# Page05_DDR4L_eMMC.net
KiCad netlist of a schematic drawn in Altium Designer
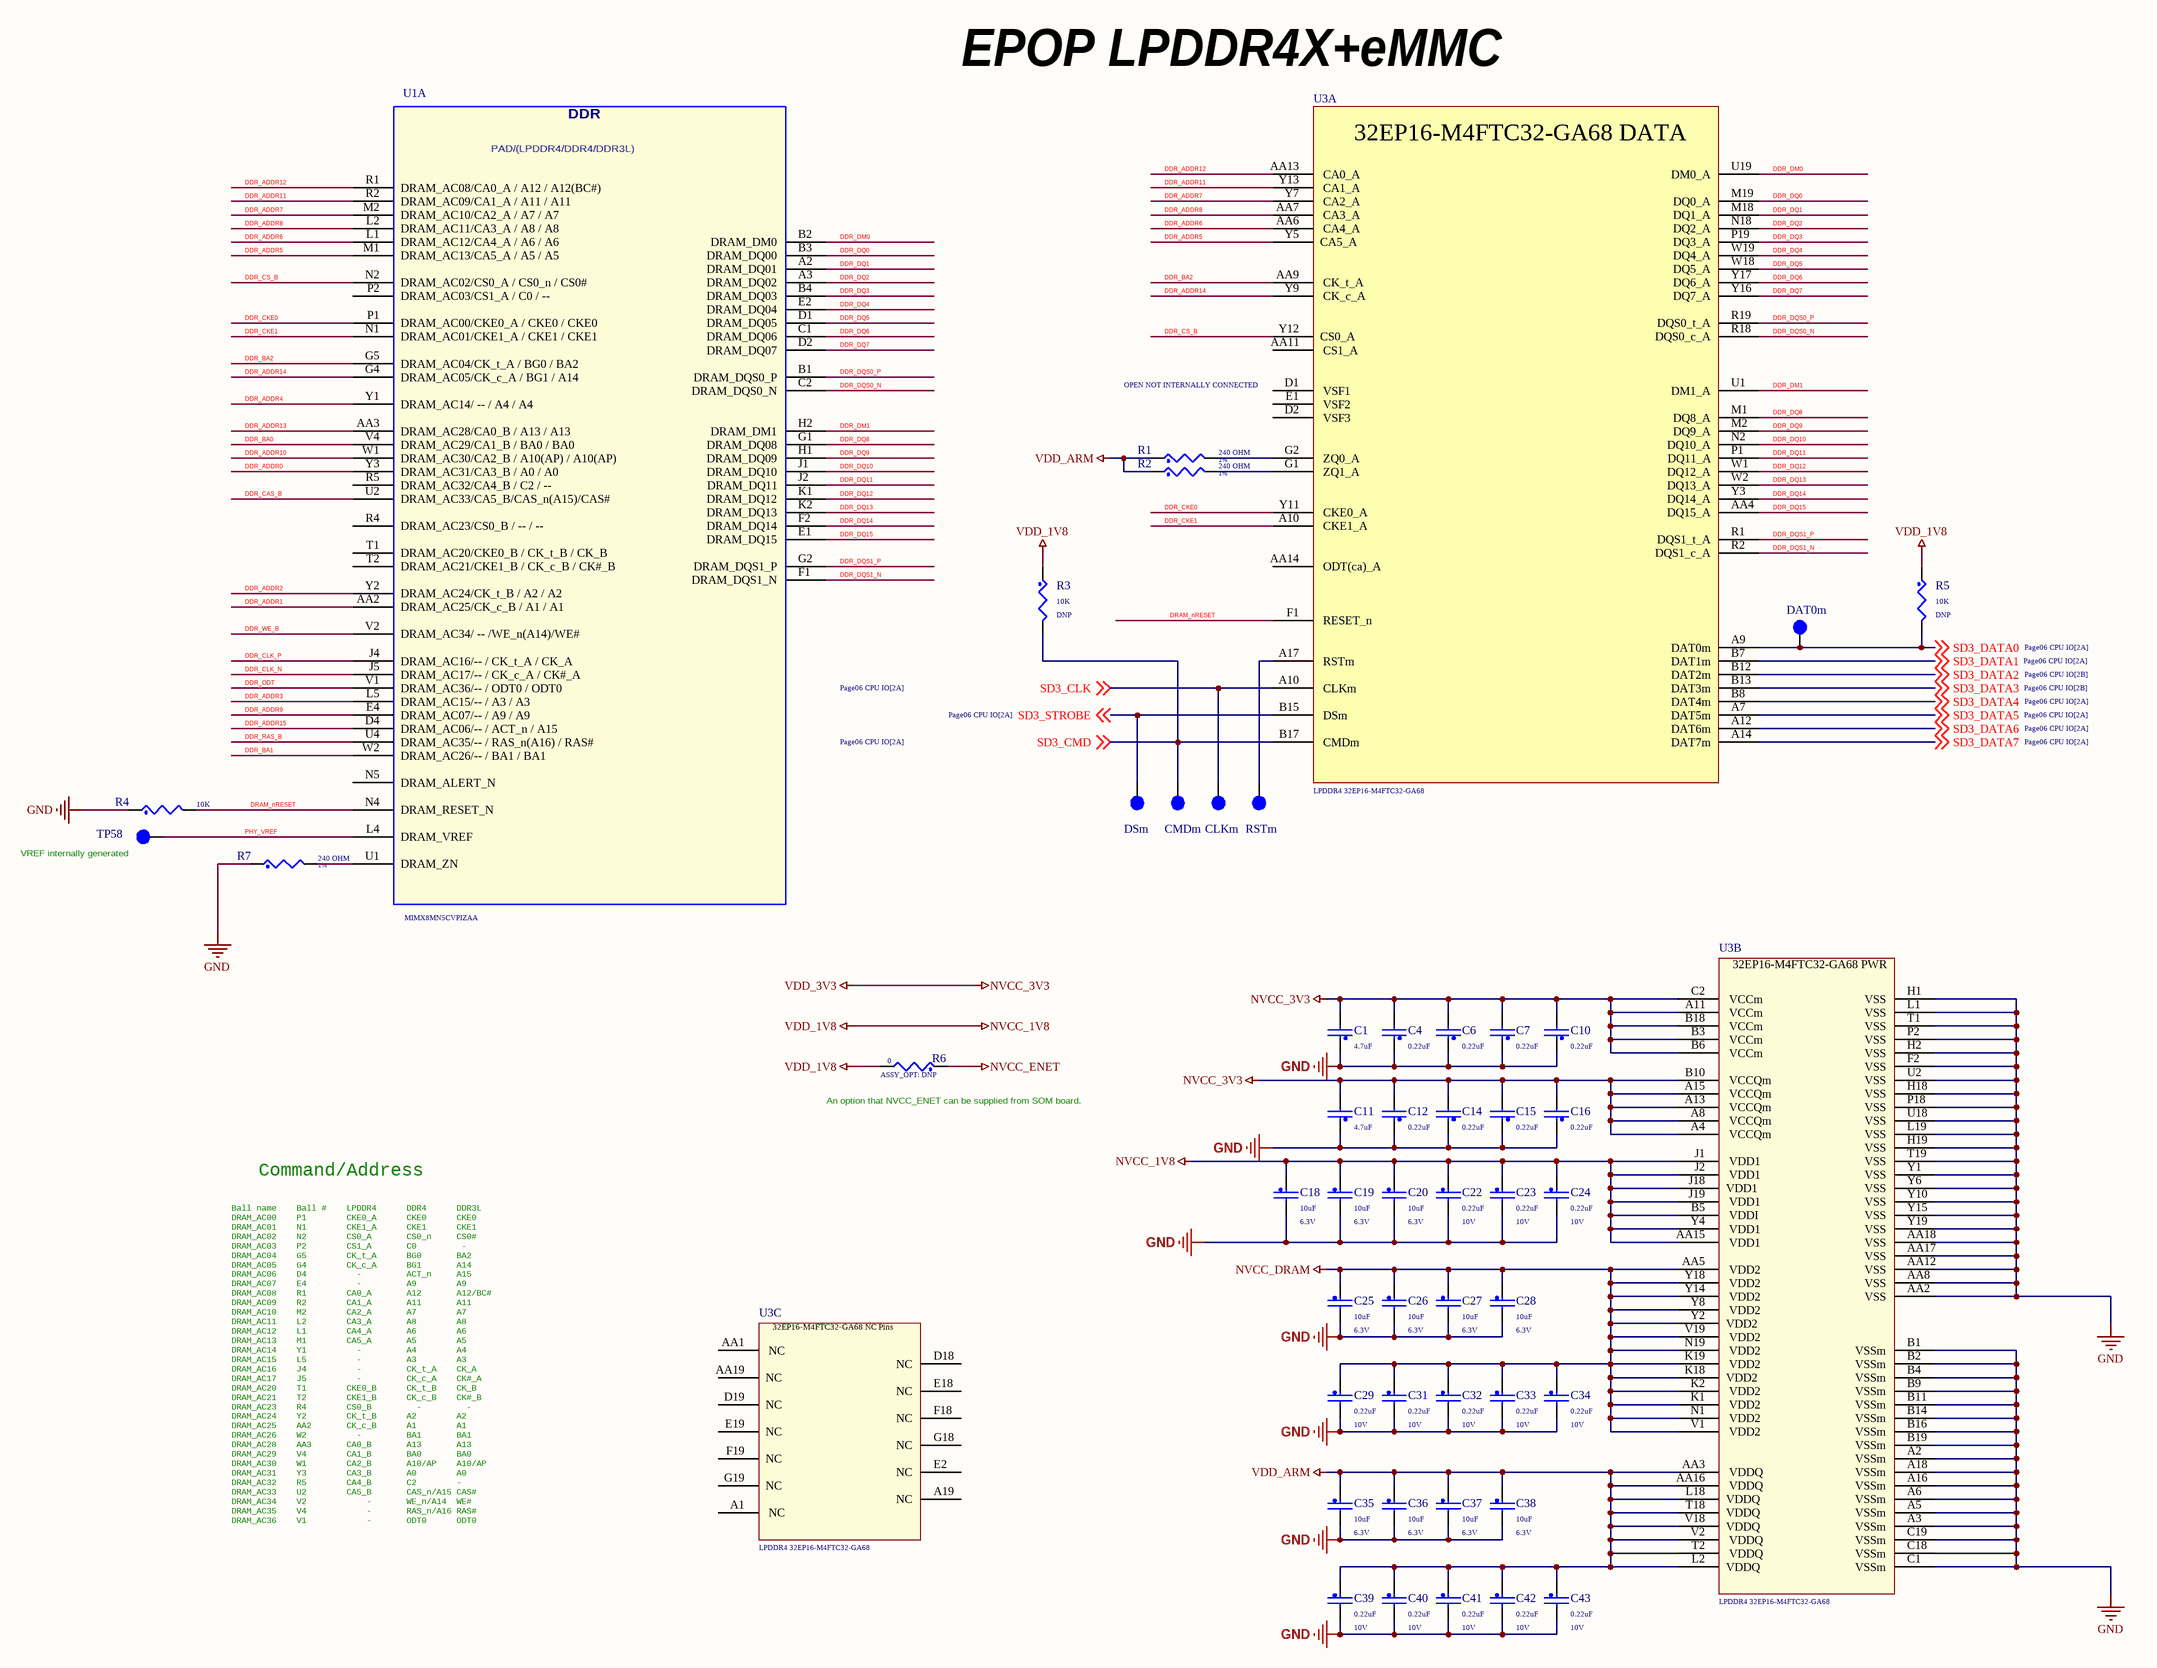
[diagram p0: Page05 DDR4L+eMMC.SchDoc]

(export (version "E")
  (design (tool "Eeschema 10.0.6"))
  (components
    (comp (ref "C1") (value "4.7uF") (footprint "0402_CC - C") (libsource (lib "AA_iMX8_M_") (part "CAP_NP")))
    (comp (ref "C4")
      (value "0.22uF")
      (footprint "0201_CC - C")
      (libsource (lib "AA_iMX8_M_") (part "CAP_NP"))
    )
    (comp (ref "C6")
      (value "0.22uF")
      (footprint "0201_CC - C")
      (libsource (lib "AA_iMX8_M_") (part "CAP_NP"))
    )
    (comp (ref "C7")
      (value "0.22uF")
      (footprint "0201_CC - C")
      (libsource (lib "AA_iMX8_M_") (part "CAP_NP"))
    )
    (comp (ref "C10")
      (value "0.22uF")
      (footprint "0201_CC - C")
      (libsource (lib "AA_iMX8_M_") (part "CAP_NP"))
    )
    (comp (ref "C11")
      (value "4.7uF")
      (footprint "0402_CC - C")
      (libsource (lib "AA_iMX8_M_") (part "CAP_NP"))
    )
    (comp (ref "C12")
      (value "0.22uF")
      (footprint "0201_CC - C")
      (libsource (lib "AA_iMX8_M_") (part "CAP_NP"))
    )
    (comp (ref "C14")
      (value "0.22uF")
      (footprint "0201_CC - C")
      (libsource (lib "AA_iMX8_M_") (part "CAP_NP"))
    )
    (comp (ref "C15")
      (value "0.22uF")
      (footprint "0201_CC - C")
      (libsource (lib "AA_iMX8_M_") (part "CAP_NP"))
    )
    (comp (ref "C16")
      (value "0.22uF")
      (footprint "0201_CC - C")
      (libsource (lib "AA_iMX8_M_") (part "CAP_NP"))
    )
    (comp (ref "C18")
      (value "10uF")
      (footprint "0402_CC - C")
      (fields (field (name "VOLTAGE") "6.3V"))
      (libsource (lib "AA_iMX8_M_") (part "CAP_NP"))
    )
    (comp (ref "C19")
      (value "10uF")
      (footprint "0402_CC - C")
      (fields (field (name "VOLTAGE") "6.3V"))
      (libsource (lib "AA_iMX8_M_") (part "CAP_NP"))
    )
    (comp (ref "C20")
      (value "10uF")
      (footprint "0402_CC - C")
      (fields (field (name "VOLTAGE") "6.3V"))
      (libsource (lib "AA_iMX8_M_") (part "CAP_NP"))
    )
    (comp (ref "C22")
      (value "0.22uF")
      (footprint "0201_CC - C")
      (fields (field (name "VOLTAGE") "10V"))
      (libsource (lib "AA_iMX8_M_") (part "CAP_NP"))
    )
    (comp (ref "C23")
      (value "0.22uF")
      (footprint "0201_CC - C")
      (fields (field (name "VOLTAGE") "10V"))
      (libsource (lib "AA_iMX8_M_") (part "CAP_NP"))
    )
    (comp (ref "C24")
      (value "0.22uF")
      (footprint "0201_CC - C")
      (fields (field (name "VOLTAGE") "10V"))
      (libsource (lib "AA_iMX8_M_") (part "CAP_NP"))
    )
    (comp (ref "C25")
      (value "10uF")
      (footprint "0402_CC - C")
      (fields (field (name "VOLTAGE") "6.3V"))
      (libsource (lib "AA_iMX8_M_") (part "CAP_NP"))
    )
    (comp (ref "C26")
      (value "10uF")
      (footprint "0402_CC - C")
      (fields (field (name "VOLTAGE") "6.3V"))
      (libsource (lib "AA_iMX8_M_") (part "CAP_NP"))
    )
    (comp (ref "C27")
      (value "10uF")
      (footprint "0402_CC - C")
      (fields (field (name "VOLTAGE") "6.3V"))
      (libsource (lib "AA_iMX8_M_") (part "CAP_NP"))
    )
    (comp (ref "C28")
      (value "10uF")
      (footprint "0402_CC - C")
      (fields (field (name "VOLTAGE") "6.3V"))
      (libsource (lib "AA_iMX8_M_") (part "CAP_NP"))
    )
    (comp (ref "C29")
      (value "0.22uF")
      (footprint "0201_CC - C")
      (fields (field (name "VOLTAGE") "10V"))
      (libsource (lib "AA_iMX8_M_") (part "CAP_NP"))
    )
    (comp (ref "C31")
      (value "0.22uF")
      (footprint "0201_CC - C")
      (fields (field (name "VOLTAGE") "10V"))
      (libsource (lib "AA_iMX8_M_") (part "CAP_NP"))
    )
    (comp (ref "C32")
      (value "0.22uF")
      (footprint "0201_CC - C")
      (fields (field (name "VOLTAGE") "10V"))
      (libsource (lib "AA_iMX8_M_") (part "CAP_NP"))
    )
    (comp (ref "C33")
      (value "0.22uF")
      (footprint "0201_CC - C")
      (fields (field (name "VOLTAGE") "10V"))
      (libsource (lib "AA_iMX8_M_") (part "CAP_NP"))
    )
    (comp (ref "C34")
      (value "0.22uF")
      (footprint "0201_CC - C")
      (fields (field (name "VOLTAGE") "10V"))
      (libsource (lib "AA_iMX8_M_") (part "CAP_NP"))
    )
    (comp (ref "C35")
      (value "10uF")
      (footprint "0402_CC - C")
      (fields (field (name "VOLTAGE") "6.3V"))
      (libsource (lib "AA_iMX8_M_") (part "CAP_NP"))
    )
    (comp (ref "C36")
      (value "10uF")
      (footprint "0402_CC - C")
      (fields (field (name "VOLTAGE") "6.3V"))
      (libsource (lib "AA_iMX8_M_") (part "CAP_NP"))
    )
    (comp (ref "C37")
      (value "10uF")
      (footprint "0402_CC - C")
      (fields (field (name "VOLTAGE") "6.3V"))
      (libsource (lib "AA_iMX8_M_") (part "CAP_NP"))
    )
    (comp (ref "C38")
      (value "10uF")
      (footprint "0402_CC - C")
      (fields (field (name "VOLTAGE") "6.3V"))
      (libsource (lib "AA_iMX8_M_") (part "CAP_NP"))
    )
    (comp (ref "C39")
      (value "0.22uF")
      (footprint "0201_CC - C")
      (fields (field (name "VOLTAGE") "10V"))
      (libsource (lib "AA_iMX8_M_") (part "CAP_NP"))
    )
    (comp (ref "C40")
      (value "0.22uF")
      (footprint "0201_CC - C")
      (fields (field (name "VOLTAGE") "10V"))
      (libsource (lib "AA_iMX8_M_") (part "CAP_NP"))
    )
    (comp (ref "C41")
      (value "0.22uF")
      (footprint "0201_CC - C")
      (fields (field (name "VOLTAGE") "10V"))
      (libsource (lib "AA_iMX8_M_") (part "CAP_NP"))
    )
    (comp (ref "C42")
      (value "0.22uF")
      (footprint "0201_CC - C")
      (fields (field (name "VOLTAGE") "10V"))
      (libsource (lib "AA_iMX8_M_") (part "CAP_NP"))
    )
    (comp (ref "C43")
      (value "0.22uF")
      (footprint "0201_CC - C")
      (fields (field (name "VOLTAGE") "10V"))
      (libsource (lib "AA_iMX8_M_") (part "CAP_NP"))
    )
    (comp (ref "CLKm")
      (value "tpad_020")
      (footprint "Test Pin")
      (description "TEST POINT PAD 0.5MM DIA SMT, NO PART TO ORDER")
      (libsource (lib "*") (part "TESTLOOP"))
    )
    (comp (ref "CMDm")
      (value "TPAD_015")
      (footprint "Test Pin")
      (description "TEST POINT PAD 15MIL DIA SMT, NO PART TO ORDER")
      (libsource (lib "*") (part "TESTLOOP"))
    )
    (comp (ref "DAT0m")
      (value "tpad_020")
      (footprint "Test Pin")
      (description "TEST POINT PAD 0.5MM DIA SMT, NO PART TO ORDER")
      (libsource (lib "*") (part "TESTLOOP"))
    )
    (comp (ref "DSm")
      (value "TPAD_015")
      (footprint "Test Pin")
      (description "TEST POINT PAD 15MIL DIA SMT, NO PART TO ORDER")
      (libsource (lib "*") (part "TESTLOOP"))
    )
    (comp (ref "R1")
      (value "240 OHM")
      (footprint "0201_RES")
      (description "RES MF 240 OHM 1/20W 1% 0201")
      (fields (field (name "VOLTAGE") "25V") (field (name "TOLERANCE") "1%"))
      (libsource (lib "*") (part "RES"))
    )
    (comp (ref "R2")
      (value "240 OHM")
      (footprint "0201_RES")
      (description "RES MF 240 OHM 1/20W 1% 0201")
      (fields (field (name "VOLTAGE") "25V") (field (name "TOLERANCE") "1%"))
      (libsource (lib "*") (part "RES"))
    )
    (comp (ref "R3")
      (value "10K")
      (footprint "0201_RES")
      (description "RES MF 10K 1/20W 5% 0201")
      (fields (field (name "ASSY_OPT") "DNP") (field (name "TOLERANCE") "5%"))
      (libsource (lib "*") (part "RES"))
    )
    (comp (ref "R4")
      (value "10K")
      (footprint "0201_RES")
      (description "RES MF 10K 1/20W 5% 0201")
      (fields (field (name "TOLERANCE") "5%"))
      (libsource (lib "*") (part "RES"))
    )
    (comp (ref "R5")
      (value "10K")
      (footprint "0201_RES")
      (description "RES MF 10K 1/20W 5% 0201")
      (fields (field (name "ASSY_OPT") "DNP") (field (name "TOLERANCE") "5%"))
      (libsource (lib "*") (part "RES"))
    )
    (comp (ref "R6")
      (value "0")
      (footprint "0402_CC_RES")
      (description "RES MF ZERO OHM 1/16W 5% 0402")
      (fields
        (field (name "ASSY_OPT") "DNP")
        (field (name "TOLERANCE") "5%")
        (field (name "VOLTAGE") "1/16W")
      )
      (libsource (lib "*") (part "RES"))
    )
    (comp (ref "R7")
      (value "240 OHM")
      (footprint "0201_RES")
      (description "RES MF 240 OHM 1/20W 1% 0201")
      (fields (field (name "VOLTAGE") "25V") (field (name "TOLERANCE") "1%"))
      (libsource (lib "*") (part "RES"))
    )
    (comp (ref "RSTm")
      (value "tpad_020")
      (footprint "Test Pin")
      (description "TEST POINT PAD 0.5MM DIA SMT, NO PART TO ORDER")
      (libsource (lib "*") (part "TESTLOOP"))
    )
    (comp (ref "TP58")
      (value "tpad_020")
      (footprint "Test Pin")
      (description "TEST POINT PAD 0.5MM DIA SMT, NO PART TO ORDER")
      (libsource (lib "*") (part "TESTLOOP"))
    )
    (comp (ref "U1")
      (value "MIMX8MN5CVPIZAA")
      (footprint "BGA306C50P21X21_1100X1100X101")
      (description "IC CPU QUAD CORTEX A53+M7 1.4GHZ -- BGA306")
      (libsource (lib "*") (part "MIMX8MN"))
    )
    (comp (ref "U3")
      (value "LPDDR4 32EP16-M4FTC32-GA68")
      (footprint "FBGA144C40P19X21_800X950X80")
      (libsource (lib "Altium starter project NANO") (part "LPDDR4 32EP16-M4FTC32-GA68"))
    )
  )
  (nets
    (net (code "1") (name "/DDR_ADDR0") (class "Default")
      (node (ref "U1") (pin "Y3") (pinfunction "DRAM_AC31/CA3_B_/_A0_/_A0_Y3") (pintype "passive"))
    )
    (net (code "2") (name "/DDR_ADDR1") (class "Default")
      (node (ref "U1") (pin "AA2") (pinfunction "DRAM_AC25/CK_c_B_/_A1_/_A1_AA2") (pintype "passive"))
    )
    (net (code "3") (name "/DDR_ADDR2") (class "Default")
      (node (ref "U1") (pin "Y2") (pinfunction "DRAM_AC24/CK_t_B_/_A2_/_A2_Y2") (pintype "passive"))
    )
    (net (code "4") (name "/DDR_ADDR3") (class "Default")
      (node (ref "U1") (pin "L5") (pinfunction "DRAM_AC15/--_/_A3_/_A3_L5") (pintype "passive"))
    )
    (net (code "5") (name "/DDR_ADDR4") (class "Default")
      (node (ref "U1") (pin "Y1") (pinfunction "DRAM_AC14/_--_/_A4_/_A4_Y1") (pintype "passive"))
    )
    (net (code "6") (name "/DDR_ADDR5") (class "Default")
      (node (ref "U1") (pin "M1") (pinfunction "DRAM_AC13/CA5_A_/_A5_/_A5_M1") (pintype "passive"))
      (node (ref "U3") (pin "Y5") (pinfunction "CA5_A_Y5") (pintype "passive"))
    )
    (net (code "7") (name "/DDR_ADDR6") (class "Default")
      (node (ref "U1") (pin "L1") (pinfunction "DRAM_AC12/CA4_A_/_A6_/_A6_L1") (pintype "passive"))
      (node (ref "U3") (pin "AA6") (pinfunction "_CA4_A_AA6") (pintype "passive"))
    )
    (net (code "8") (name "/DDR_ADDR7") (class "Default")
      (node (ref "U1") (pin "M2") (pinfunction "DRAM_AC10/CA2_A_/_A7_/_A7_M2") (pintype "passive"))
      (node (ref "U3") (pin "Y7") (pinfunction "_CA2_A_Y7") (pintype "passive"))
    )
    (net (code "9") (name "/DDR_ADDR8") (class "Default")
      (node (ref "U1") (pin "L2") (pinfunction "DRAM_AC11/CA3_A_/_A8_/_A8_L2") (pintype "passive"))
      (node (ref "U3") (pin "AA7") (pinfunction "_CA3_A_AA7") (pintype "passive"))
    )
    (net (code "10") (name "/DDR_ADDR9") (class "Default")
      (node (ref "U1") (pin "E4") (pinfunction "DRAM_AC07/--_/_A9_/_A9_E4") (pintype "passive"))
    )
    (net (code "11") (name "/DDR_ADDR10") (class "Default")
      (node (ref "U1") (pin "W1") (pinfunction "DRAM_AC30/CA2_B_/_A10(AP)_/_A10(AP)_W1") (pintype "passive"))
    )
    (net (code "12") (name "/DDR_ADDR11") (class "Default")
      (node (ref "U1") (pin "R2") (pinfunction "DRAM_AC09/CA1_A_/_A11_/_A11_R2") (pintype "passive"))
      (node (ref "U3") (pin "Y13") (pinfunction "_CA1_A_Y13") (pintype "passive"))
    )
    (net (code "13") (name "/DDR_ADDR12") (class "Default")
      (node (ref "U1") (pin "R1") (pinfunction "DRAM_AC08/CA0_A_/_A12_/_A12(BC#)_R1") (pintype "passive"))
      (node (ref "U3") (pin "AA13") (pinfunction "_CA0_A_AA13") (pintype "passive"))
    )
    (net (code "14") (name "/DDR_ADDR13") (class "Default")
      (node (ref "U1") (pin "AA3") (pinfunction "DRAM_AC28/CA0_B_/_A13_/_A13_AA3") (pintype "passive"))
    )
    (net (code "15") (name "/DDR_ADDR14") (class "Default")
      (node (ref "U1") (pin "G4") (pinfunction "DRAM_AC05/CK_c_A_/_BG1_/_A14_G4") (pintype "passive"))
      (node (ref "U3") (pin "Y9") (pinfunction "_CK_c_A_Y9") (pintype "passive"))
    )
    (net (code "16") (name "/DDR_ADDR15") (class "Default")
      (node (ref "U1") (pin "D4") (pinfunction "DRAM_AC06/--_/_ACT_n_/_A15_D4") (pintype "passive"))
    )
    (net (code "17") (name "/DDR_BA0") (class "Default")
      (node (ref "U1") (pin "V4") (pinfunction "DRAM_AC29/CA1_B_/_BA0_/_BA0_V4") (pintype "passive"))
    )
    (net (code "18") (name "/DDR_BA1") (class "Default")
      (node (ref "U1") (pin "W2") (pinfunction "DRAM_AC26/--_/_BA1_/_BA1_W2") (pintype "passive"))
    )
    (net (code "19") (name "/DDR_BA2") (class "Default")
      (node (ref "U1") (pin "G5") (pinfunction "DRAM_AC04/CK_t_A_/_BG0_/_BA2_G5") (pintype "passive"))
      (node (ref "U3") (pin "AA9") (pinfunction "_CK_t_A_AA9") (pintype "passive"))
    )
    (net (code "20") (name "/DDR_CAS_B") (class "Default")
      (node (ref "U1") (pin "U2") (pinfunction "DRAM_AC33/CA5_B/CAS_n(A15)/CAS#_U2") (pintype "passive"))
    )
    (net (code "21") (name "/DDR_CKE0") (class "Default")
      (node (ref "U1") (pin "P1") (pinfunction "DRAM_AC00/CKE0_A_/_CKE0_/_CKE0_P1") (pintype "passive"))
      (node (ref "U3") (pin "Y11") (pinfunction "_CKE0_A_Y11") (pintype "passive"))
    )
    (net (code "22") (name "/DDR_CKE1") (class "Default")
      (node (ref "U1") (pin "N1") (pinfunction "DRAM_AC01/CKE1_A_/_CKE1_/_CKE1_N1") (pintype "passive"))
      (node (ref "U3") (pin "A10") (pinfunction "_CKE1_A_A10") (pintype "passive"))
    )
    (net (code "23") (name "/DDR_CLK_N") (class "Default")
      (node (ref "U1") (pin "J5") (pinfunction "DRAM_AC17/--_/_CK_c_A_/_CK#_A_J5") (pintype "passive"))
    )
    (net (code "24") (name "/DDR_CLK_P") (class "Default")
      (node (ref "U1") (pin "J4") (pinfunction "DRAM_AC16/--_/_CK_t_A_/_CK_A_J4") (pintype "passive"))
    )
    (net (code "25") (name "/DDR_CS_B") (class "Default")
      (node (ref "U1") (pin "N2") (pinfunction "DRAM_AC02/CS0_A_/_CS0_n_/_CS0#_N2") (pintype "passive"))
      (node (ref "U3") (pin "Y12") (pinfunction "CS0_A_Y12") (pintype "passive"))
    )
    (net (code "26") (name "/DDR_DM0") (class "Default")
      (node (ref "U1") (pin "B2") (pinfunction "DRAM_DM0_B2") (pintype "passive"))
      (node (ref "U3") (pin "U19") (pinfunction "_DM0_A_U19") (pintype "passive"))
    )
    (net (code "27") (name "/DDR_DM1") (class "Default")
      (node (ref "U1") (pin "H2") (pinfunction "DRAM_DM1_H2") (pintype "passive"))
      (node (ref "U3") (pin "U1") (pinfunction "_DM1_A_U1") (pintype "passive"))
    )
    (net (code "28") (name "/DDR_DQ0") (class "Default")
      (node (ref "U1") (pin "B3") (pinfunction "DRAM_DQ00_B3") (pintype "passive"))
      (node (ref "U3") (pin "M19") (pinfunction "_DQ0_A_M19") (pintype "passive"))
    )
    (net (code "29") (name "/DDR_DQ1") (class "Default")
      (node (ref "U1") (pin "A2") (pinfunction "DRAM_DQ01_A2") (pintype "passive"))
      (node (ref "U3") (pin "M18") (pinfunction "DQ1_A_M18") (pintype "passive"))
    )
    (net (code "30") (name "/DDR_DQ2") (class "Default")
      (node (ref "U1") (pin "A3") (pinfunction "DRAM_DQ02_A3") (pintype "passive"))
      (node (ref "U3") (pin "N18") (pinfunction "DQ2_A_N18") (pintype "passive"))
    )
    (net (code "31") (name "/DDR_DQ3") (class "Default")
      (node (ref "U1") (pin "B4") (pinfunction "DRAM_DQ03_B4") (pintype "passive"))
      (node (ref "U3") (pin "P19") (pinfunction "DQ3_A_P19") (pintype "passive"))
    )
    (net (code "32") (name "/DDR_DQ4") (class "Default")
      (node (ref "U1") (pin "E2") (pinfunction "DRAM_DQ04_E2") (pintype "passive"))
      (node (ref "U3") (pin "W19") (pinfunction "_DQ4_A_W19") (pintype "passive"))
    )
    (net (code "33") (name "/DDR_DQ5") (class "Default")
      (node (ref "U1") (pin "D1") (pinfunction "DRAM_DQ05_D1") (pintype "passive"))
      (node (ref "U3") (pin "W18") (pinfunction "DQ5_A_W18") (pintype "passive"))
    )
    (net (code "34") (name "/DDR_DQ6") (class "Default")
      (node (ref "U1") (pin "C1") (pinfunction "DRAM_DQ06_C1") (pintype "passive"))
      (node (ref "U3") (pin "Y17") (pinfunction "_DQ6_A_Y17") (pintype "passive"))
    )
    (net (code "35") (name "/DDR_DQ7") (class "Default")
      (node (ref "U1") (pin "D2") (pinfunction "DRAM_DQ07_D2") (pintype "passive"))
      (node (ref "U3") (pin "Y16") (pinfunction "_DQ7_A_Y16") (pintype "passive"))
    )
    (net (code "36") (name "/DDR_DQ8") (class "Default")
      (node (ref "U1") (pin "G1") (pinfunction "DRAM_DQ08_G1") (pintype "passive"))
      (node (ref "U3") (pin "M1") (pinfunction "_DQ8_A_M1") (pintype "passive"))
    )
    (net (code "37") (name "/DDR_DQ9") (class "Default")
      (node (ref "U1") (pin "H1") (pinfunction "DRAM_DQ09_H1") (pintype "passive"))
      (node (ref "U3") (pin "M2") (pinfunction "_DQ9_A_M2") (pintype "passive"))
    )
    (net (code "38") (name "/DDR_DQ10") (class "Default")
      (node (ref "U1") (pin "J1") (pinfunction "DRAM_DQ10_J1") (pintype "passive"))
      (node (ref "U3") (pin "N2") (pinfunction "_DQ10_A_N2") (pintype "passive"))
    )
    (net (code "39") (name "/DDR_DQ11") (class "Default")
      (node (ref "U1") (pin "J2") (pinfunction "DRAM_DQ11_J2") (pintype "passive"))
      (node (ref "U3") (pin "P1") (pinfunction "_DQ11_A_P1") (pintype "passive"))
    )
    (net (code "40") (name "/DDR_DQ12") (class "Default")
      (node (ref "U1") (pin "K1") (pinfunction "DRAM_DQ12_K1") (pintype "passive"))
      (node (ref "U3") (pin "W1") (pinfunction "_DQ12_A_W1") (pintype "passive"))
    )
    (net (code "41") (name "/DDR_DQ13") (class "Default")
      (node (ref "U1") (pin "K2") (pinfunction "DRAM_DQ13_K2") (pintype "passive"))
      (node (ref "U3") (pin "W2") (pinfunction "_DQ13_A_W2") (pintype "passive"))
    )
    (net (code "42") (name "/DDR_DQ14") (class "Default")
      (node (ref "U1") (pin "F2") (pinfunction "DRAM_DQ14_F2") (pintype "passive"))
      (node (ref "U3") (pin "Y3") (pinfunction "_DQ14_A_Y3") (pintype "passive"))
    )
    (net (code "43") (name "/DDR_DQ15") (class "Default")
      (node (ref "U1") (pin "E1") (pinfunction "DRAM_DQ15_E1") (pintype "passive"))
      (node (ref "U3") (pin "AA4") (pinfunction "_DQ15_A_AA4") (pintype "passive"))
    )
    (net (code "44") (name "/DDR_DQS0_N") (class "Default")
      (node (ref "U1") (pin "C2") (pinfunction "DRAM_DQS0_N_C2") (pintype "passive"))
      (node (ref "U3") (pin "R18") (pinfunction "DQS0_c_A_R18") (pintype "passive"))
    )
    (net (code "45") (name "/DDR_DQS0_P") (class "Default")
      (node (ref "U1") (pin "B1") (pinfunction "DRAM_DQS0_P_B1") (pintype "passive"))
      (node (ref "U3") (pin "R19") (pinfunction "_DQS0_t_A_R19") (pintype "passive"))
    )
    (net (code "46") (name "/DDR_DQS1_N") (class "Default")
      (node (ref "U1") (pin "F1") (pinfunction "DRAM_DQS1_N_F1") (pintype "passive"))
      (node (ref "U3") (pin "R2") (pinfunction "_DQS1_c_A_R2") (pintype "passive"))
    )
    (net (code "47") (name "/DDR_DQS1_P") (class "Default")
      (node (ref "U1") (pin "G2") (pinfunction "DRAM_DQS1_P_G2") (pintype "passive"))
      (node (ref "U3") (pin "R1") (pinfunction "_DQS1_t_A_R1") (pintype "passive"))
    )
    (net (code "48") (name "/DDR_ODT") (class "Default")
      (node (ref "U1") (pin "V1") (pinfunction "DRAM_AC36/--_/_ODT0_/_ODT0_V1") (pintype "passive"))
    )
    (net (code "49") (name "/DDR_RAS_B") (class "Default")
      (node (ref "U1") (pin "U4") (pinfunction "DRAM_AC35/--_/_RAS_n(A16)_/_RAS#_U4") (pintype "passive"))
    )
    (net (code "50") (name "/DDR_WE_B") (class "Default")
      (node (ref "U1") (pin "V2") (pinfunction "DRAM_AC34/_--_/WE_n(A14)/WE#_V2") (pintype "passive"))
    )
    (net (code "51") (name "/DRAM_nRESET") (class "Default")
      (node (ref "R4") (pin "2") (pinfunction "2_2") (pintype "passive"))
      (node (ref "U1") (pin "N4") (pinfunction "DRAM_RESET_N_N4") (pintype "passive"))
      (node (ref "U3") (pin "F1") (pinfunction "_RESET_n_F1") (pintype "passive"))
    )
    (net (code "52") (name "/PHY_VREF") (class "Default")
      (node (ref "TP58") (pin "1") (pinfunction "Pin1_1") (pintype "passive"))
      (node (ref "U1") (pin "L4") (pinfunction "DRAM_VREF_L4") (pintype "passive"))
    )
    (net (code "53") (name "GND") (class "Default")
      (node (ref "C1") (pin "1") (pinfunction "1_1") (pintype "passive"))
      (node (ref "C10") (pin "1") (pinfunction "1_1") (pintype "passive"))
      (node (ref "C11") (pin "1") (pinfunction "1_1") (pintype "passive"))
      (node (ref "C12") (pin "1") (pinfunction "1_1") (pintype "passive"))
      (node (ref "C14") (pin "1") (pinfunction "1_1") (pintype "passive"))
      (node (ref "C15") (pin "1") (pinfunction "1_1") (pintype "passive"))
      (node (ref "C16") (pin "1") (pinfunction "1_1") (pintype "passive"))
      (node (ref "C18") (pin "2") (pinfunction "2_2") (pintype "passive"))
      (node (ref "C19") (pin "2") (pinfunction "2_2") (pintype "passive"))
      (node (ref "C20") (pin "2") (pinfunction "2_2") (pintype "passive"))
      (node (ref "C22") (pin "2") (pinfunction "2_2") (pintype "passive"))
      (node (ref "C23") (pin "2") (pinfunction "2_2") (pintype "passive"))
      (node (ref "C24") (pin "2") (pinfunction "2_2") (pintype "passive"))
      (node (ref "C25") (pin "2") (pinfunction "2_2") (pintype "passive"))
      (node (ref "C26") (pin "2") (pinfunction "2_2") (pintype "passive"))
      (node (ref "C27") (pin "2") (pinfunction "2_2") (pintype "passive"))
      (node (ref "C28") (pin "2") (pinfunction "2_2") (pintype "passive"))
      (node (ref "C29") (pin "2") (pinfunction "2_2") (pintype "passive"))
      (node (ref "C31") (pin "2") (pinfunction "2_2") (pintype "passive"))
      (node (ref "C32") (pin "2") (pinfunction "2_2") (pintype "passive"))
      (node (ref "C33") (pin "2") (pinfunction "2_2") (pintype "passive"))
      (node (ref "C34") (pin "2") (pinfunction "2_2") (pintype "passive"))
      (node (ref "C35") (pin "2") (pinfunction "2_2") (pintype "passive"))
      (node (ref "C36") (pin "2") (pinfunction "2_2") (pintype "passive"))
      (node (ref "C37") (pin "2") (pinfunction "2_2") (pintype "passive"))
      (node (ref "C38") (pin "2") (pinfunction "2_2") (pintype "passive"))
      (node (ref "C39") (pin "2") (pinfunction "2_2") (pintype "passive"))
      (node (ref "C4") (pin "1") (pinfunction "1_1") (pintype "passive"))
      (node (ref "C40") (pin "2") (pinfunction "2_2") (pintype "passive"))
      (node (ref "C41") (pin "2") (pinfunction "2_2") (pintype "passive"))
      (node (ref "C42") (pin "2") (pinfunction "2_2") (pintype "passive"))
      (node (ref "C43") (pin "2") (pinfunction "2_2") (pintype "passive"))
      (node (ref "C6") (pin "1") (pinfunction "1_1") (pintype "passive"))
      (node (ref "C7") (pin "1") (pinfunction "1_1") (pintype "passive"))
      (node (ref "R4") (pin "1") (pinfunction "1_1") (pintype "passive"))
      (node (ref "R7") (pin "1") (pinfunction "1_1") (pintype "passive"))
      (node (ref "U3") (pin "A16") (pinfunction "_VSSm_A16") (pintype "power_in"))
      (node (ref "U3") (pin "A18") (pinfunction "_VSSm_A18") (pintype "power_in"))
      (node (ref "U3") (pin "A2") (pinfunction "_VSSm_A2") (pintype "power_in"))
      (node (ref "U3") (pin "A3") (pinfunction "VSSm_A3") (pintype "power_in"))
      (node (ref "U3") (pin "A5") (pinfunction "_VSSm_A5") (pintype "power_in"))
      (node (ref "U3") (pin "A6") (pinfunction "_VSSm_A6") (pintype "power_in"))
      (node (ref "U3") (pin "AA12") (pinfunction "_VSS_AA12") (pintype "power_in"))
      (node (ref "U3") (pin "AA17") (pinfunction "_VSS_AA17") (pintype "power_in"))
      (node (ref "U3") (pin "AA18") (pinfunction "VSS_AA18") (pintype "power_in"))
      (node (ref "U3") (pin "AA2") (pinfunction "VSS_AA2") (pintype "power_in"))
      (node (ref "U3") (pin "AA8") (pinfunction "_VSS_AA8") (pintype "power_in"))
      (node (ref "U3") (pin "B1") (pinfunction "_VSSm_B1") (pintype "power_in"))
      (node (ref "U3") (pin "B11") (pinfunction "_VSSm_B11") (pintype "power_in"))
      (node (ref "U3") (pin "B14") (pinfunction "_VSSm_B14") (pintype "power_in"))
      (node (ref "U3") (pin "B16") (pinfunction "_VSSm_B16") (pintype "power_in"))
      (node (ref "U3") (pin "B19") (pinfunction "_VSSm_B19") (pintype "power_in"))
      (node (ref "U3") (pin "B2") (pinfunction "_VSSm_B2") (pintype "power_in"))
      (node (ref "U3") (pin "B4") (pinfunction "_VSSm_B4") (pintype "power_in"))
      (node (ref "U3") (pin "B9") (pinfunction "_VSSm_B9") (pintype "power_in"))
      (node (ref "U3") (pin "C1") (pinfunction "_VSSm_C1") (pintype "power_in"))
      (node (ref "U3") (pin "C18") (pinfunction "VSSm_C18") (pintype "power_in"))
      (node (ref "U3") (pin "C19") (pinfunction "_VSSm_C19") (pintype "power_in"))
      (node (ref "U3") (pin "F2") (pinfunction "_VSS_F2") (pintype "power_in"))
      (node (ref "U3") (pin "H1") (pinfunction "_VSS_H1") (pintype "power_in"))
      (node (ref "U3") (pin "H18") (pinfunction "VSS_H18") (pintype "power_in"))
      (node (ref "U3") (pin "H19") (pinfunction "VSS_H19") (pintype "power_in"))
      (node (ref "U3") (pin "H2") (pinfunction "VSS_H2") (pintype "power_in"))
      (node (ref "U3") (pin "L1") (pinfunction "_VSS_L1") (pintype "power_in"))
      (node (ref "U3") (pin "L19") (pinfunction "VSS_L19") (pintype "power_in"))
      (node (ref "U3") (pin "P18") (pinfunction "VSS_P18") (pintype "power_in"))
      (node (ref "U3") (pin "P2") (pinfunction "_VSS_P2") (pintype "power_in"))
      (node (ref "U3") (pin "T1") (pinfunction "_VSS_T1") (pintype "power_in"))
      (node (ref "U3") (pin "T19") (pinfunction "VSS_T19") (pintype "power_in"))
      (node (ref "U3") (pin "U18") (pinfunction "VSS_U18") (pintype "power_in"))
      (node (ref "U3") (pin "U2") (pinfunction "_VSS_U2") (pintype "power_in"))
      (node (ref "U3") (pin "Y1") (pinfunction "_VSS_Y1") (pintype "power_in"))
      (node (ref "U3") (pin "Y10") (pinfunction "_VSS_Y10") (pintype "power_in"))
      (node (ref "U3") (pin "Y15") (pinfunction "_VSS_Y15") (pintype "power_in"))
      (node (ref "U3") (pin "Y19") (pinfunction "VSS_Y19") (pintype "power_in"))
      (node (ref "U3") (pin "Y6") (pinfunction "_VSS_Y6") (pintype "power_in"))
    )
    (net (code "54") (name "NVCC_1V8") (class "Default")
      (node (ref "C18") (pin "1") (pinfunction "1_1") (pintype "passive"))
      (node (ref "C19") (pin "1") (pinfunction "1_1") (pintype "passive"))
      (node (ref "C20") (pin "1") (pinfunction "1_1") (pintype "passive"))
      (node (ref "C22") (pin "1") (pinfunction "1_1") (pintype "passive"))
      (node (ref "C23") (pin "1") (pinfunction "1_1") (pintype "passive"))
      (node (ref "C24") (pin "1") (pinfunction "1_1") (pintype "passive"))
      (node (ref "R3") (pin "1") (pinfunction "1_1") (pintype "passive"))
      (node (ref "R5") (pin "1") (pinfunction "1_1") (pintype "passive"))
      (node (ref "R6") (pin "2") (pinfunction "2_2") (pintype "passive"))
      (node (ref "U3") (pin "AA15") (pinfunction "_VDD1_AA15") (pintype "power_in"))
      (node (ref "U3") (pin "B5") (pinfunction "_VDDI_B5") (pintype "power_in"))
      (node (ref "U3") (pin "J1") (pinfunction "_VDD1_J1") (pintype "power_in"))
      (node (ref "U3") (pin "J18") (pinfunction "VDD1_J18") (pintype "power_in"))
      (node (ref "U3") (pin "J19") (pinfunction "_VDD1_J19") (pintype "power_in"))
      (node (ref "U3") (pin "J2") (pinfunction "_VDD1_J2") (pintype "power_in"))
      (node (ref "U3") (pin "Y4") (pinfunction "_VDD1_Y4") (pintype "power_in"))
    )
    (net (code "55") (name "NVCC_3V3") (class "Default")
      (node (ref "C1") (pin "2") (pinfunction "2_2") (pintype "passive"))
      (node (ref "C10") (pin "2") (pinfunction "2_2") (pintype "passive"))
      (node (ref "C11") (pin "2") (pinfunction "2_2") (pintype "passive"))
      (node (ref "C12") (pin "2") (pinfunction "2_2") (pintype "passive"))
      (node (ref "C14") (pin "2") (pinfunction "2_2") (pintype "passive"))
      (node (ref "C15") (pin "2") (pinfunction "2_2") (pintype "passive"))
      (node (ref "C16") (pin "2") (pinfunction "2_2") (pintype "passive"))
      (node (ref "C4") (pin "2") (pinfunction "2_2") (pintype "passive"))
      (node (ref "C6") (pin "2") (pinfunction "2_2") (pintype "passive"))
      (node (ref "C7") (pin "2") (pinfunction "2_2") (pintype "passive"))
      (node (ref "U3") (pin "A11") (pinfunction "_VCCm_A11") (pintype "power_in"))
      (node (ref "U3") (pin "A13") (pinfunction "_VCCQm_A13") (pintype "power_in"))
      (node (ref "U3") (pin "A15") (pinfunction "_VCCQm_A15") (pintype "power_in"))
      (node (ref "U3") (pin "A4") (pinfunction "_VCCQm_A4") (pintype "power_in"))
      (node (ref "U3") (pin "A8") (pinfunction "_VCCQm_A8") (pintype "power_in"))
      (node (ref "U3") (pin "B10") (pinfunction "_VCCQm_B10") (pintype "power_in"))
      (node (ref "U3") (pin "B18") (pinfunction "_VCCm_B18") (pintype "power_in"))
      (node (ref "U3") (pin "B3") (pinfunction "_VCCm_B3") (pintype "power_in"))
      (node (ref "U3") (pin "B6") (pinfunction "_VCCm_B6") (pintype "power_in"))
      (node (ref "U3") (pin "C2") (pinfunction "_VCCm_C2") (pintype "power_in"))
    )
    (net (code "56") (name "NVCC_DRAM") (class "Default")
      (node (ref "C25") (pin "1") (pinfunction "1_1") (pintype "passive"))
      (node (ref "C26") (pin "1") (pinfunction "1_1") (pintype "passive"))
      (node (ref "C27") (pin "1") (pinfunction "1_1") (pintype "passive"))
      (node (ref "C28") (pin "1") (pinfunction "1_1") (pintype "passive"))
      (node (ref "C29") (pin "1") (pinfunction "1_1") (pintype "passive"))
      (node (ref "C31") (pin "1") (pinfunction "1_1") (pintype "passive"))
      (node (ref "C32") (pin "1") (pinfunction "1_1") (pintype "passive"))
      (node (ref "C33") (pin "1") (pinfunction "1_1") (pintype "passive"))
      (node (ref "C34") (pin "1") (pinfunction "1_1") (pintype "passive"))
      (node (ref "U3") (pin "AA5") (pinfunction "_VDD2_AA5") (pintype "power_in"))
      (node (ref "U3") (pin "K1") (pinfunction "_VDD2_K1") (pintype "power_in"))
      (node (ref "U3") (pin "K18") (pinfunction "VDD2_K18") (pintype "power_in"))
      (node (ref "U3") (pin "K19") (pinfunction "_VDD2_K19") (pintype "power_in"))
      (node (ref "U3") (pin "K2") (pinfunction "_VDD2_K2") (pintype "power_in"))
      (node (ref "U3") (pin "N1") (pinfunction "_VDD2_N1") (pintype "power_in"))
      (node (ref "U3") (pin "N19") (pinfunction "_VDD2_N19") (pintype "power_in"))
      (node (ref "U3") (pin "V1") (pinfunction "_VDD2_V1") (pintype "power_in"))
      (node (ref "U3") (pin "V19") (pinfunction "_VDD2_V19") (pintype "power_in"))
      (node (ref "U3") (pin "Y14") (pinfunction "_VDD2_Y14") (pintype "power_in"))
      (node (ref "U3") (pin "Y18") (pinfunction "_VDD2_Y18") (pintype "power_in"))
      (node (ref "U3") (pin "Y2") (pinfunction "VDD2_Y2") (pintype "power_in"))
      (node (ref "U3") (pin "Y8") (pinfunction "_VDD2_Y8") (pintype "power_in"))
    )
    (net (code "57") (name "NVCC_ENET") (class "Default")
      (node (ref "R6") (pin "1") (pinfunction "1_1") (pintype "passive"))
    )
    (net (code "58") (name "Net-(RSTm-Pin1)") (class "Default")
      (node (ref "RSTm") (pin "1") (pinfunction "Pin1_1") (pintype "passive"))
      (node (ref "U3") (pin "A17") (pinfunction "_RSTm_A17") (pintype "passive"))
    )
    (net (code "59") (name "Net-(U1A-DRAM_ZN)") (class "Default")
      (node (ref "R7") (pin "2") (pinfunction "2_2") (pintype "passive"))
      (node (ref "U1") (pin "U1") (pinfunction "DRAM_ZN_U1") (pintype "passive"))
    )
    (net (code "60") (name "Net-(U3A-_ZQ0_A)") (class "Default")
      (node (ref "R1") (pin "2") (pinfunction "2_2") (pintype "passive"))
      (node (ref "U3") (pin "G2") (pinfunction "_ZQ0_A_G2") (pintype "passive"))
    )
    (net (code "61") (name "Net-(U3A-_ZQ1_A)") (class "Default")
      (node (ref "R2") (pin "2") (pinfunction "2_2") (pintype "passive"))
      (node (ref "U3") (pin "G1") (pinfunction "_ZQ1_A_G1") (pintype "passive"))
    )
    (net (code "62") (name "SD3_CLK") (class "Default")
      (node (ref "CLKm") (pin "1") (pinfunction "Pin1_1") (pintype "passive"))
      (node (ref "U3") (pin "A10") (pinfunction "_CLKm_A10") (pintype "passive"))
    )
    (net (code "63") (name "SD3_CMD") (class "Default")
      (node (ref "CMDm") (pin "1") (pinfunction "Pin1_1") (pintype "passive"))
      (node (ref "R3") (pin "2") (pinfunction "2_2") (pintype "passive"))
      (node (ref "U3") (pin "B17") (pinfunction "_CMDm_B17") (pintype "passive"))
    )
    (net (code "64") (name "SD3_DATA0") (class "Default")
      (node (ref "DAT0m") (pin "1") (pinfunction "Pin1_1") (pintype "passive"))
      (node (ref "R5") (pin "2") (pinfunction "2_2") (pintype "passive"))
      (node (ref "U3") (pin "A9") (pinfunction "_DAT0m_A9") (pintype "passive"))
    )
    (net (code "65") (name "SD3_DATA1") (class "Default")
      (node (ref "U3") (pin "B7") (pinfunction "DAT1m_B7") (pintype "passive"))
    )
    (net (code "66") (name "SD3_DATA2") (class "Default")
      (node (ref "U3") (pin "B12") (pinfunction "_DAT2m_B12") (pintype "passive"))
    )
    (net (code "67") (name "SD3_DATA3") (class "Default")
      (node (ref "U3") (pin "B13") (pinfunction "_DAT3m_B13") (pintype "passive"))
    )
    (net (code "68") (name "SD3_DATA4") (class "Default")
      (node (ref "U3") (pin "B8") (pinfunction "_DAT4m_B8") (pintype "passive"))
    )
    (net (code "69") (name "SD3_DATA5") (class "Default")
      (node (ref "U3") (pin "A7") (pinfunction "_DAT5m_A7") (pintype "passive"))
    )
    (net (code "70") (name "SD3_DATA6") (class "Default")
      (node (ref "U3") (pin "A12") (pinfunction "_DAT6m_A12") (pintype "passive"))
    )
    (net (code "71") (name "SD3_DATA7") (class "Default")
      (node (ref "U3") (pin "A14") (pinfunction "_DAT7m_A14") (pintype "passive"))
    )
    (net (code "72") (name "SD3_STROBE") (class "Default")
      (node (ref "DSm") (pin "1") (pinfunction "Pin1_1") (pintype "passive"))
      (node (ref "U3") (pin "B15") (pinfunction "_DSm_B15") (pintype "passive"))
    )
    (net (code "73") (name "VDD_ARM") (class "Default")
      (node (ref "C35") (pin "1") (pinfunction "1_1") (pintype "passive"))
      (node (ref "C36") (pin "1") (pinfunction "1_1") (pintype "passive"))
      (node (ref "C37") (pin "1") (pinfunction "1_1") (pintype "passive"))
      (node (ref "C38") (pin "1") (pinfunction "1_1") (pintype "passive"))
      (node (ref "C39") (pin "1") (pinfunction "1_1") (pintype "passive"))
      (node (ref "C40") (pin "1") (pinfunction "1_1") (pintype "passive"))
      (node (ref "C41") (pin "1") (pinfunction "1_1") (pintype "passive"))
      (node (ref "C42") (pin "1") (pinfunction "1_1") (pintype "passive"))
      (node (ref "C43") (pin "1") (pinfunction "1_1") (pintype "passive"))
      (node (ref "R1") (pin "1") (pinfunction "1_1") (pintype "passive"))
      (node (ref "R2") (pin "1") (pinfunction "1_1") (pintype "passive"))
      (node (ref "U3") (pin "AA16") (pinfunction "_VDDQ_AA16") (pintype "power_in"))
      (node (ref "U3") (pin "AA3") (pinfunction "_VDDQ_AA3") (pintype "power_in"))
      (node (ref "U3") (pin "L18") (pinfunction "VDDQ_L18") (pintype "power_in"))
      (node (ref "U3") (pin "L2") (pinfunction "VDDQ_L2") (pintype "power_in"))
      (node (ref "U3") (pin "T18") (pinfunction "VDDQ_T18") (pintype "power_in"))
      (node (ref "U3") (pin "T2") (pinfunction "_VDDQ_T2") (pintype "power_in"))
      (node (ref "U3") (pin "V18") (pinfunction "VDDQ_V18") (pintype "power_in"))
      (node (ref "U3") (pin "V2") (pinfunction "_VDDQ_V2") (pintype "power_in"))
    )
    (net (code "74") (name "unconnected-(U1A-DRAM_AC03{slash}CS1_A_{slash}_C0_{slash}_---PadP2)") (class "Default")
      (node (ref "U1") (pin "P2") (pinfunction "DRAM_AC03/CS1_A_/_C0_/_--_P2") (pintype "passive"))
    )
    (net (code "75") (name "unconnected-(U1A-DRAM_AC20{slash}CKE0_B_{slash}_CK_t_B_{slash}_CK_B-PadT1)") (class "Default")
      (node (ref "U1") (pin "T1") (pinfunction "DRAM_AC20/CKE0_B_/_CK_t_B_/_CK_B_T1") (pintype "passive"))
    )
    (net (code "76") (name "unconnected-(U1A-DRAM_AC21{slash}CKE1_B_{slash}_CK_c_B_{slash}_CK#_B-PadT2)") (class "Default")
      (node (ref "U1") (pin "T2") (pinfunction "DRAM_AC21/CKE1_B_/_CK_c_B_/_CK#_B_T2") (pintype "passive"))
    )
    (net (code "77") (name "unconnected-(U1A-DRAM_AC23{slash}CS0_B_{slash}_--_{slash}_---PadR4)") (class "Default")
      (node (ref "U1") (pin "R4") (pinfunction "DRAM_AC23/CS0_B_/_--_/_--_R4") (pintype "passive"))
    )
    (net (code "78") (name "unconnected-(U1A-DRAM_AC32{slash}CA4_B_{slash}_C2_{slash}_---PadR5)") (class "Default")
      (node (ref "U1") (pin "R5") (pinfunction "DRAM_AC32/CA4_B_/_C2_/_--_R5") (pintype "passive"))
    )
    (net (code "79") (name "unconnected-(U1A-DRAM_ALERT_N-PadN5)") (class "Default")
      (node (ref "U1") (pin "N5") (pinfunction "DRAM_ALERT_N_N5") (pintype "passive"))
    )
    (net (code "80") (name "unconnected-(U3A-_CS1_A-PadAA11)") (class "Default")
      (node (ref "U3") (pin "AA11") (pinfunction "_CS1_A_AA11") (pintype "passive"))
    )
    (net (code "81") (name "unconnected-(U3A-_ODT(ca)_A-PadAA14)") (class "Default")
      (node (ref "U3") (pin "AA14") (pinfunction "_ODT(ca)_A_AA14") (pintype "passive"))
    )
    (net (code "82") (name "unconnected-(U3A-_VSF1-PadD1)") (class "Default")
      (node (ref "U3") (pin "D1") (pinfunction "_VSF1_D1") (pintype "passive"))
    )
    (net (code "83") (name "unconnected-(U3A-_VSF2-PadE1)") (class "Default")
      (node (ref "U3") (pin "E1") (pinfunction "_VSF2_E1") (pintype "passive"))
    )
    (net (code "84") (name "unconnected-(U3A-_VSF3-PadD2)") (class "Default")
      (node (ref "U3") (pin "D2") (pinfunction "_VSF3_D2") (pintype "passive"))
    )
    (net (code "85") (name "unconnected-(U3C-NC-PadA19)") (class "Default")
      (node (ref "U3") (pin "A19") (pinfunction "NC_A19") (pintype "passive"))
    )
    (net (code "86") (name "unconnected-(U3C-NC-PadAA19)") (class "Default")
      (node (ref "U3") (pin "AA19") (pinfunction "NC_AA19") (pintype "passive"))
    )
    (net (code "87") (name "unconnected-(U3C-NC-PadD18)") (class "Default")
      (node (ref "U3") (pin "D18") (pinfunction "NC_D18") (pintype "passive"))
    )
    (net (code "88") (name "unconnected-(U3C-NC-PadD19)") (class "Default")
      (node (ref "U3") (pin "D19") (pinfunction "NC_D19") (pintype "passive"))
    )
    (net (code "89") (name "unconnected-(U3C-NC-PadE2)") (class "Default")
      (node (ref "U3") (pin "E2") (pinfunction "NC_E2") (pintype "passive"))
    )
    (net (code "90") (name "unconnected-(U3C-NC-PadE18)") (class "Default")
      (node (ref "U3") (pin "E18") (pinfunction "NC_E18") (pintype "passive"))
    )
    (net (code "91") (name "unconnected-(U3C-NC-PadE19)") (class "Default")
      (node (ref "U3") (pin "E19") (pinfunction "NC_E19") (pintype "passive"))
    )
    (net (code "92") (name "unconnected-(U3C-NC-PadF18)") (class "Default")
      (node (ref "U3") (pin "F18") (pinfunction "NC_F18") (pintype "passive"))
    )
    (net (code "93") (name "unconnected-(U3C-NC-PadF19)") (class "Default")
      (node (ref "U3") (pin "F19") (pinfunction "NC_F19") (pintype "passive"))
    )
    (net (code "94") (name "unconnected-(U3C-NC-PadG18)") (class "Default")
      (node (ref "U3") (pin "G18") (pinfunction "NC_G18") (pintype "passive"))
    )
    (net (code "95") (name "unconnected-(U3C-NC-PadG19)") (class "Default")
      (node (ref "U3") (pin "G19") (pinfunction "NC_G19") (pintype "passive"))
    )
    (net (code "96") (name "unconnected-(U3C-_NC-PadA1)") (class "Default")
      (node (ref "U3") (pin "A1") (pinfunction "_NC_A1") (pintype "passive"))
    )
    (net (code "97") (name "unconnected-(U3C-_NC-PadAA1)") (class "Default")
      (node (ref "U3") (pin "AA1") (pinfunction "_NC_AA1") (pintype "passive"))
    )
  )
)
